# UP-4_v8.net
KiCad netlist of a schematic drawn in EAGLE
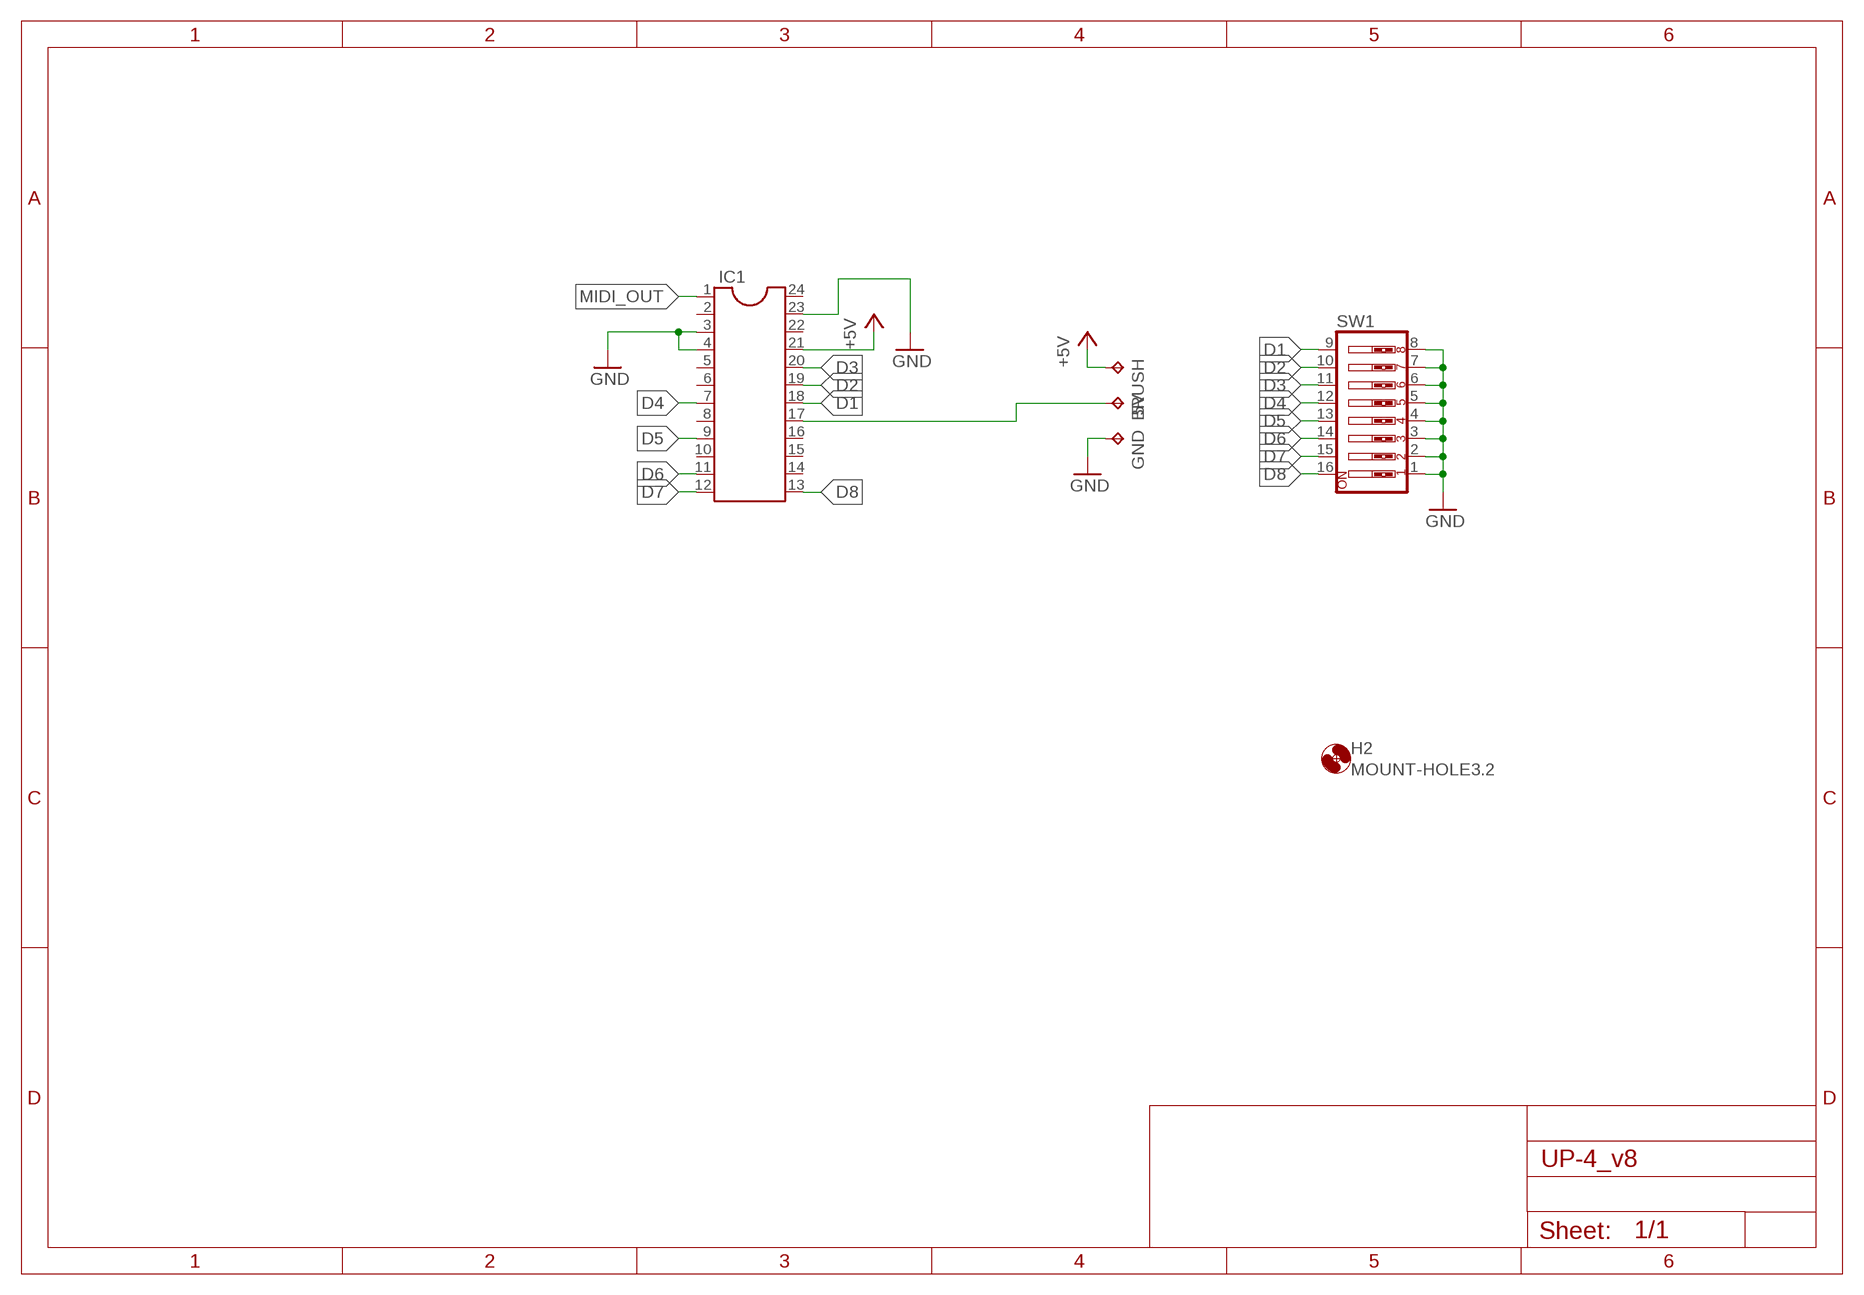
[diagram p0: schematic, sheet 1]

(export (version "E")
  (design (tool "Eeschema 10.0.6"))
  (components
    (comp (ref "5V")
      (value "TPB2,54")
      (footprint "eagle-import:B2,54")
      (libsource (lib "eagle-import") (part "TPB2,54"))
    )
    (comp (ref "BRUSH")
      (value "TPB2,54")
      (footprint "eagle-import:B2,54")
      (libsource (lib "eagle-import") (part "TPB2,54"))
    )
    (comp (ref "GND")
      (value "TPB2,54")
      (footprint "eagle-import:B2,54")
      (libsource (lib "eagle-import") (part "TPB2,54"))
    )
    (comp (ref "H2")
      (value "MOUNT-HOLE3.2")
      (footprint "eagle-import:3,2")
      (libsource (lib "eagle-import") (part "MOUNT-HOLE3.2"))
    )
    (comp (ref "IC1")
      (value "DIL24-6")
      (footprint "eagle-import:DIL24-6")
      (libsource (lib "eagle-import") (part "DIL24-6"))
    )
    (comp (ref "SW1")
      (value "SW_DIP-8")
      (footprint "eagle-import:EDG-08")
      (libsource (lib "eagle-import") (part "SW_DIP-8"))
    )
  )
  (nets
    (net (code "1") (name "+5V") (class "Default")
      (node (ref "BRUSH") (pin "TP") (pinfunction "TP_TP") (pintype "input"))
      (node (ref "IC1") (pin "21") (pinfunction "21_21") (pintype "passive"))
    )
    (net (code "2") (name "D1") (class "Default")
      (node (ref "IC1") (pin "18") (pinfunction "18_18") (pintype "passive"))
      (node (ref "SW1") (pin "9") (pinfunction "9_9") (pintype "passive"))
    )
    (net (code "3") (name "D2") (class "Default")
      (node (ref "IC1") (pin "19") (pinfunction "19_19") (pintype "passive"))
      (node (ref "SW1") (pin "10") (pinfunction "10_10") (pintype "passive"))
    )
    (net (code "4") (name "D3") (class "Default")
      (node (ref "IC1") (pin "20") (pinfunction "20_20") (pintype "passive"))
      (node (ref "SW1") (pin "11") (pinfunction "11_11") (pintype "passive"))
    )
    (net (code "5") (name "D4") (class "Default")
      (node (ref "IC1") (pin "7") (pinfunction "7_7") (pintype "passive"))
      (node (ref "SW1") (pin "12") (pinfunction "12_12") (pintype "passive"))
    )
    (net (code "6") (name "D5") (class "Default")
      (node (ref "IC1") (pin "9") (pinfunction "9_9") (pintype "passive"))
      (node (ref "SW1") (pin "13") (pinfunction "13_13") (pintype "passive"))
    )
    (net (code "7") (name "D6") (class "Default")
      (node (ref "IC1") (pin "11") (pinfunction "11_11") (pintype "passive"))
      (node (ref "SW1") (pin "14") (pinfunction "14_14") (pintype "passive"))
    )
    (net (code "8") (name "D7") (class "Default")
      (node (ref "IC1") (pin "12") (pinfunction "12_12") (pintype "passive"))
      (node (ref "SW1") (pin "15") (pinfunction "15_15") (pintype "passive"))
    )
    (net (code "9") (name "D8") (class "Default")
      (node (ref "IC1") (pin "13") (pinfunction "13_13") (pintype "passive"))
      (node (ref "SW1") (pin "16") (pinfunction "16_16") (pintype "passive"))
    )
    (net (code "10") (name "GND") (class "Default")
      (node (ref "GND") (pin "TP") (pinfunction "TP_TP") (pintype "input"))
      (node (ref "IC1") (pin "23") (pinfunction "23_23") (pintype "passive"))
      (node (ref "IC1") (pin "3") (pinfunction "3_3") (pintype "passive"))
      (node (ref "IC1") (pin "4") (pinfunction "4_4") (pintype "passive"))
      (node (ref "SW1") (pin "1") (pinfunction "1_1") (pintype "passive"))
      (node (ref "SW1") (pin "2") (pinfunction "2_2") (pintype "passive"))
      (node (ref "SW1") (pin "3") (pinfunction "3_3") (pintype "passive"))
      (node (ref "SW1") (pin "4") (pinfunction "4_4") (pintype "passive"))
      (node (ref "SW1") (pin "5") (pinfunction "5_5") (pintype "passive"))
      (node (ref "SW1") (pin "6") (pinfunction "6_6") (pintype "passive"))
      (node (ref "SW1") (pin "7") (pinfunction "7_7") (pintype "passive"))
      (node (ref "SW1") (pin "8") (pinfunction "8_8") (pintype "passive"))
    )
    (net (code "11") (name "MIDI_OUT") (class "Default")
      (node (ref "IC1") (pin "1") (pinfunction "1_1") (pintype "passive"))
    )
    (net (code "12") (name "Net-(5V-PadTP)") (class "Default")
      (node (ref "5V") (pin "TP") (pinfunction "TP_TP") (pintype "input"))
      (node (ref "IC1") (pin "17") (pinfunction "17_17") (pintype "passive"))
    )
    (net (code "13") (name "unconnected-(IC1-Pad2)") (class "Default")
      (node (ref "IC1") (pin "2") (pinfunction "2_2") (pintype "passive"))
    )
    (net (code "14") (name "unconnected-(IC1-Pad5)") (class "Default")
      (node (ref "IC1") (pin "5") (pinfunction "5_5") (pintype "passive"))
    )
    (net (code "15") (name "unconnected-(IC1-Pad6)") (class "Default")
      (node (ref "IC1") (pin "6") (pinfunction "6_6") (pintype "passive"))
    )
    (net (code "16") (name "unconnected-(IC1-Pad8)") (class "Default")
      (node (ref "IC1") (pin "8") (pinfunction "8_8") (pintype "passive"))
    )
    (net (code "17") (name "unconnected-(IC1-Pad10)") (class "Default")
      (node (ref "IC1") (pin "10") (pinfunction "10_10") (pintype "passive"))
    )
    (net (code "18") (name "unconnected-(IC1-Pad14)") (class "Default")
      (node (ref "IC1") (pin "14") (pinfunction "14_14") (pintype "passive"))
    )
    (net (code "19") (name "unconnected-(IC1-Pad15)") (class "Default")
      (node (ref "IC1") (pin "15") (pinfunction "15_15") (pintype "passive"))
    )
    (net (code "20") (name "unconnected-(IC1-Pad16)") (class "Default")
      (node (ref "IC1") (pin "16") (pinfunction "16_16") (pintype "passive"))
    )
    (net (code "21") (name "unconnected-(IC1-Pad22)") (class "Default")
      (node (ref "IC1") (pin "22") (pinfunction "22_22") (pintype "passive"))
    )
    (net (code "22") (name "unconnected-(IC1-Pad24)") (class "Default")
      (node (ref "IC1") (pin "24") (pinfunction "24_24") (pintype "passive"))
    )
  )
)
